# Driver2.net
KiCad netlist of a schematic drawn in Altium Designer
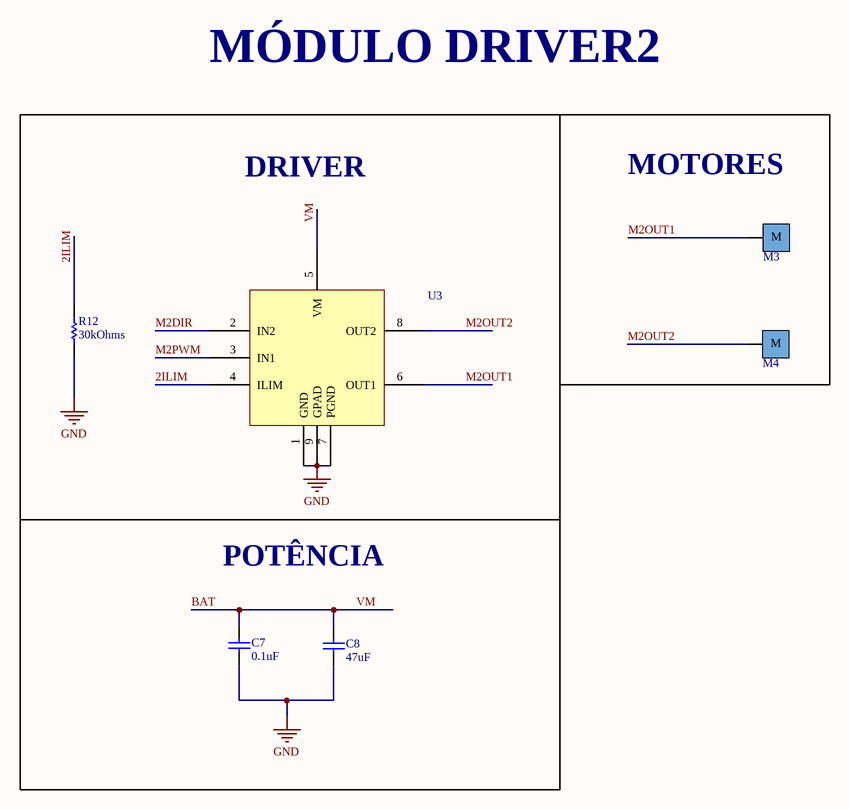
[diagram p0: Driver2.SchDoc]

(export (version "E")
  (design (tool "Eeschema 10.0.6"))
  (components
    (comp (ref "C7")
      (value "0.1uF")
      (footprint "C0805")
      (description "CAP CER 100nF 25V X7R 0805")
      (fields
        (field (name "MANUFACTURER") "Kemet")
        (field (name "PART NUMBER") "C0805C104M3RACTU")
        (field (name "LIBRARY CONTROL - PERSON THAT CHECKED FOOTPRINT") "Cage")
        (field (name "LIBRARY CONTROL - PERSON THAT CHECKED SCHEMATIC") "Cage")
        (field (name "LIBRARY CONTROL - PERSON THAT DID THE LAST UPDATE FOOTPRINT") "Cage")
        (field (name "LIBRARY CONTROL - PERSON THAT DID THE LAST UPDATE SCHEMATIC") "Cage")
      )
      (libsource (lib "Uai!Tecas") (part "C0805C104M3RACTU"))
    )
    (comp (ref "C8")
      (value "47uF")
      (footprint "C1210")
      (description "CAP CER 47uF 16V X6S 1210")
      (fields
        (field (name "MANUFACTURER") "Murata")
        (field (name "PART NUMBER") "GRM32EC81C476KE15K")
        (field (name "LIBRARY CONTROL - PERSON THAT CHECKED FOOTPRINT") "Cage")
        (field (name "LIBRARY CONTROL - PERSON THAT CHECKED SCHEMATIC") "Cage")
        (field (name "LIBRARY CONTROL - PERSON THAT DID THE LAST UPDATE FOOTPRINT") "Prisma")
        (field (name "LIBRARY CONTROL - PERSON THAT DID THE LAST UPDATE SCHEMATIC") "Prisma")
      )
      (libsource (lib "Capacitor") (part "GRM32EC81C476KE15K"))
    )
    (comp (ref "M3")
      (value "Motor Pad")
      (footprint "PAD_MOTOR_MINI")
      (description "MOTOR PAD MINI SUMÔ")
      (libsource (lib "Uai!Tecas") (part "Motor Pad Mini Sumô"))
    )
    (comp (ref "M4")
      (value "Motor Pad")
      (footprint "PAD_MOTOR_MINI")
      (description "MOTOR PAD MINI SUMÔ")
      (libsource (lib "Uai!Tecas") (part "Motor Pad Mini Sumô"))
    )
    (comp (ref "R12")
      (value "30kOhms")
      (footprint "RESC1608X55N")
      (description "RES SMD 30 kOHMS 1% 1/10W 0603")
      (fields
        (field (name "MANUFACTURER") "YAGEO")
        (field (name "PART NUMBER") "RC0603FR-0730KL")
        (field (name "LIBRARY CONTROL - PERSON THAT CHECKED FOOTPRINT") "Guilherme")
        (field (name "LIBRARY CONTROL - PERSON THAT CHECKED SCHEMATIC") "Guilherme")
        (field (name "LIBRARY CONTROL - PERSON THAT DID THE LAST UPDATE FOOTPRINT") "Guilherme")
        (field (name "LIBRARY CONTROL - PERSON THAT DID THE LAST UPDATE SCHEMATIC") "Guilherme")
      )
      (libsource (lib "Uai!Tecas") (part "RC0603FR-0730KL"))
    )
    (comp (ref "U3")
      (value "DRV8871DDA")
      (footprint "SO-PowerPad-8(8_pins)")
      (description "IC MTR DRV (6.5V ~ 45V) (3.5 A) SO-PowerPad-8")
      (fields
        (field (name "MANUFACTURER") "Texas Instruments")
        (field (name "LIBRARY CONTROL - PERSON THAT CHECKED SCHEMATIC") "Stéfany (Ster)")
        (field (name "LIBRARY CONTROL - PERSON THAT CHECKED FOOTPRINT") "Stéfany (Ster)")
        (field (name "LIBRARY CONTROL - PERSON THAT DID THE LAST UPDATE SCHEMATIC") "Stéfany (Ster)")
        (field (name "LIBRARY CONTROL - PERSON THAT DID THE LAST UPDATE FOOTPRINT") "Maria Laura")
      )
      (libsource (lib "Uai!Tecas") (part "DRV8871DDA"))
    )
  )
  (nets
    (net (code "1") (name "/2ILIM") (class "Default")
      (node (ref "R12") (pin "1") (pinfunction "1_1") (pintype "passive"))
      (node (ref "U3") (pin "4") (pinfunction "ILIM_4") (pintype "passive"))
    )
    (net (code "2") (name "/BAT") (class "Default")
      (node (ref "C7") (pin "2") (pinfunction "2_2") (pintype "passive"))
      (node (ref "C8") (pin "2") (pinfunction "2_2") (pintype "passive"))
      (node (ref "U3") (pin "5") (pinfunction "VM_5") (pintype "passive"))
    )
    (net (code "3") (name "/M2DIR") (class "Default")
      (node (ref "U3") (pin "2") (pinfunction "IN2_2") (pintype "passive"))
    )
    (net (code "4") (name "/M2OUT1") (class "Default")
      (node (ref "M3") (pin "M") (pinfunction "M_M") (pintype "passive"))
      (node (ref "U3") (pin "6") (pinfunction "OUT1_6") (pintype "passive"))
    )
    (net (code "5") (name "/M2OUT2") (class "Default")
      (node (ref "M4") (pin "M") (pinfunction "M_M") (pintype "passive"))
      (node (ref "U3") (pin "8") (pinfunction "OUT2_8") (pintype "passive"))
    )
    (net (code "6") (name "/M2PWM") (class "Default")
      (node (ref "U3") (pin "3") (pinfunction "IN1_3") (pintype "passive"))
    )
    (net (code "7") (name "GND") (class "Default")
      (node (ref "C7") (pin "1") (pinfunction "1_1") (pintype "passive"))
      (node (ref "C8") (pin "1") (pinfunction "1_1") (pintype "passive"))
      (node (ref "R12") (pin "2") (pinfunction "2_2") (pintype "passive"))
      (node (ref "U3") (pin "1") (pinfunction "GND_1") (pintype "passive"))
      (node (ref "U3") (pin "7") (pinfunction "PGND_7") (pintype "passive"))
      (node (ref "U3") (pin "9") (pinfunction "GPAD_9") (pintype "passive"))
    )
  )
)
